# Schematic.net
KiCad netlist of a schematic drawn in Altium Designer
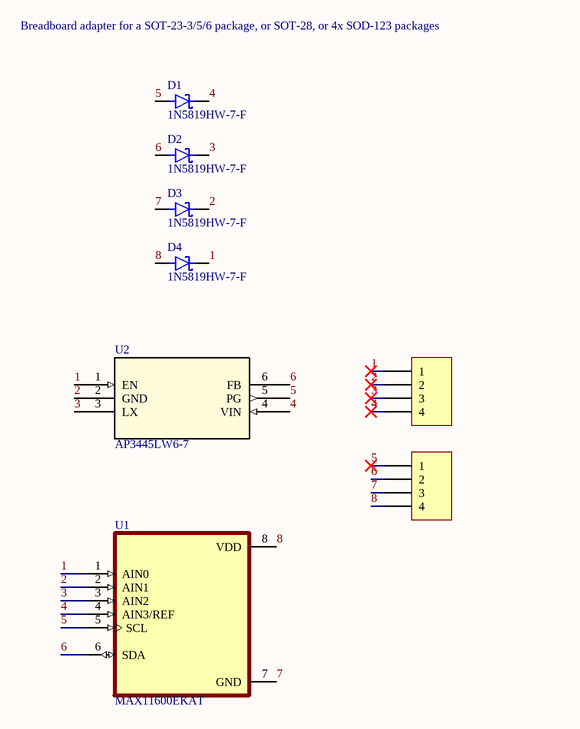
[diagram p0: Schematic.SchDoc]

(export (version "E")
  (design (tool "Eeschema 10.0.6"))
  (components
    (comp (ref "D1")
      (value "1N5819HW-7-F")
      (footprint "SOD3715X145N")
      (description "Diode Schottky 40 V 1A Surface Mount SOD-123")
      (fields (field (name "MF") "Diodes Inc."))
      (libsource (lib "1N5819HW-7-F") (part "1N5819HW-7-F"))
    )
    (comp (ref "D2")
      (value "1N5819HW-7-F")
      (footprint "SOD3715X145N")
      (description "Diode Schottky 40 V 1A Surface Mount SOD-123")
      (fields (field (name "MF") "Diodes Inc."))
      (libsource (lib "1N5819HW-7-F") (part "1N5819HW-7-F"))
    )
    (comp (ref "D3")
      (value "1N5819HW-7-F")
      (footprint "SOD3715X145N")
      (description "Diode Schottky 40 V 1A Surface Mount SOD-123")
      (fields (field (name "MF") "Diodes Inc."))
      (libsource (lib "1N5819HW-7-F") (part "1N5819HW-7-F"))
    )
    (comp (ref "D4")
      (value "1N5819HW-7-F")
      (footprint "SOD3715X145N")
      (description "Diode Schottky 40 V 1A Surface Mount SOD-123")
      (fields (field (name "MF") "Diodes Inc."))
      (libsource (lib "1N5819HW-7-F") (part "1N5819HW-7-F"))
    )
    (comp (ref "P1")
      (value "Header 4")
      (footprint "HDR1X4")
      (description "Header, 4-Pin")
      (fields (field (name "PUBLISHER") "Altium Limited"))
      (libsource (lib "Miscellaneous Connectors") (part "Header 4"))
    )
    (comp (ref "P2")
      (value "Header 4")
      (footprint "HDR1X4")
      (description "Header, 4-Pin")
      (fields (field (name "PUBLISHER") "Altium Limited"))
      (libsource (lib "Miscellaneous Connectors") (part "Header 4"))
    )
    (comp (ref "U1")
      (value "MAX11600EKAT")
      (footprint "SOT65P280X145-8N")
      (description "8 Bit Analog to Digital Converter 2, 4 Input 1 SAR SOT-23-8")
      (fields (field (name "MP") "MAX11600EKA+T") (field (name "MF") "Maxim Integrated"))
      (libsource (lib "MAX11600EKAT") (part "MAX11600EKAT"))
    )
    (comp (ref "U2")
      (value "AP3445LW6-7")
      (footprint "SOT26_AP3445_DIO")
      (description "No Description Available")
      (fields (field (name "COPYRIGHT") "Copyright (C) 2024 Ultra Librarian. All rights reserved."))
      (libsource (lib "AP3445LW6-7") (part "AP3445LW6-7"))
    )
  )
  (nets
    (net (code "1") (name "/1") (class "Default")
      (node (ref "D4") (pin "C") (pinfunction "K_C") (pintype "passive"))
      (node (ref "P1") (pin "1") (pinfunction "1_1") (pintype "passive"))
      (node (ref "U1") (pin "1") (pinfunction "AIN0_1") (pintype "input"))
      (node (ref "U2") (pin "1") (pinfunction "EN_1") (pintype "input"))
    )
    (net (code "2") (name "/2") (class "Default")
      (node (ref "D3") (pin "C") (pinfunction "K_C") (pintype "passive"))
      (node (ref "P1") (pin "2") (pinfunction "2_2") (pintype "passive"))
      (node (ref "U1") (pin "2") (pinfunction "AIN1_2") (pintype "input"))
      (node (ref "U2") (pin "2") (pinfunction "GND_2") (pintype "power_in"))
    )
    (net (code "3") (name "/3") (class "Default")
      (node (ref "D2") (pin "C") (pinfunction "K_C") (pintype "passive"))
      (node (ref "P1") (pin "3") (pinfunction "3_3") (pintype "passive"))
      (node (ref "U1") (pin "3") (pinfunction "AIN2_3") (pintype "input"))
      (node (ref "U2") (pin "3") (pinfunction "LX_3") (pintype "passive"))
    )
    (net (code "4") (name "/4") (class "Default")
      (node (ref "D1") (pin "C") (pinfunction "K_C") (pintype "passive"))
      (node (ref "P1") (pin "4") (pinfunction "4_4") (pintype "passive"))
      (node (ref "U1") (pin "4") (pinfunction "AIN3/REF_4") (pintype "input"))
      (node (ref "U2") (pin "4") (pinfunction "VIN_4") (pintype "input"))
    )
    (net (code "5") (name "/5") (class "Default")
      (node (ref "D1") (pin "A") (pinfunction "A_A") (pintype "passive"))
      (node (ref "P2") (pin "1") (pinfunction "1_1") (pintype "passive"))
      (node (ref "U1") (pin "5") (pinfunction "SCL_5") (pintype "input"))
      (node (ref "U2") (pin "5") (pinfunction "PG_5") (pintype "output"))
    )
    (net (code "6") (name "/6") (class "Default")
      (node (ref "D2") (pin "A") (pinfunction "A_A") (pintype "passive"))
      (node (ref "P2") (pin "2") (pinfunction "2_2") (pintype "passive"))
      (node (ref "U1") (pin "6") (pinfunction "SDA_6") (pintype "bidirectional"))
      (node (ref "U2") (pin "6") (pinfunction "FB_6") (pintype "passive"))
    )
    (net (code "7") (name "/7") (class "Default")
      (node (ref "D3") (pin "A") (pinfunction "A_A") (pintype "passive"))
      (node (ref "P2") (pin "3") (pinfunction "3_3") (pintype "passive"))
      (node (ref "U1") (pin "7") (pinfunction "GND_7") (pintype "power_in"))
    )
    (net (code "8") (name "/8") (class "Default")
      (node (ref "D4") (pin "A") (pinfunction "A_A") (pintype "passive"))
      (node (ref "P2") (pin "4") (pinfunction "4_4") (pintype "passive"))
      (node (ref "U1") (pin "8") (pinfunction "VDD_8") (pintype "power_in"))
    )
  )
)
